# Decawave.net
KiCad netlist of a schematic drawn in Altium Designer
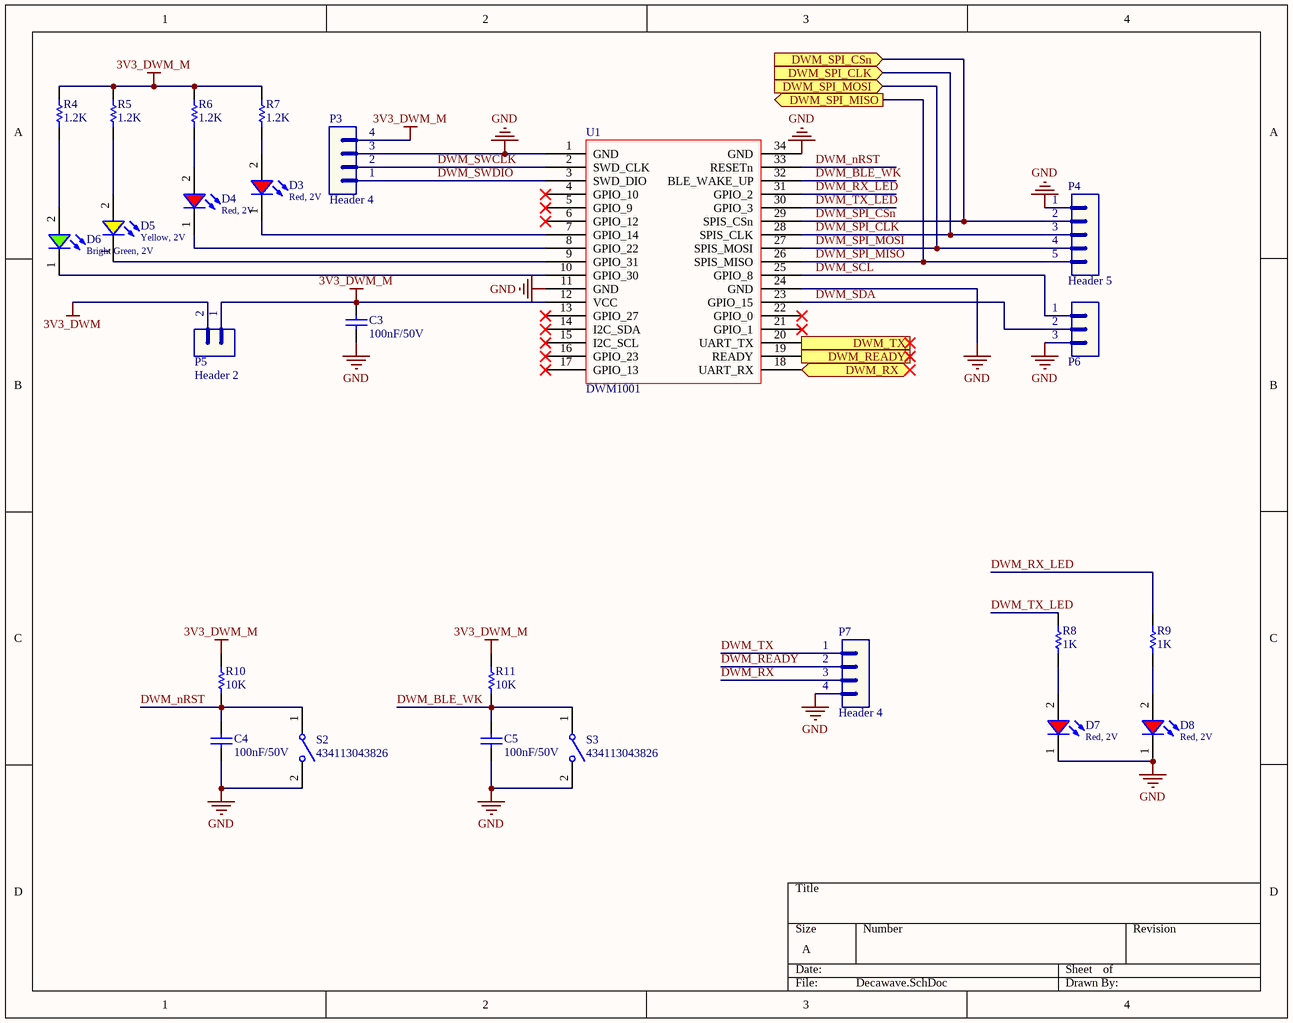
[diagram p0: Decawave.SchDoc]

(export (version "E")
  (design (tool "Eeschema 10.0.6"))
  (components
    (comp (ref "C3")
      (value "100nF/50V")
      (footprint "CAP-SM-0805")
      (description "CAP CER 0.1UF 50V Y5V 0805")
      (fields
        (field (name "MANUFACTURER") "Samsung Electro-Mechanics")
        (field (name "MANUFACTURER PART NUMBER") "CL21F104ZBCNNNC")
      )
      (libsource (lib "Capacitor") (part "Cap-100nF-50V-0805"))
    )
    (comp (ref "C4")
      (value "100nF/50V")
      (footprint "CAP-SM-0805")
      (description "CAP CER 0.1UF 50V Y5V 0805")
      (fields
        (field (name "MANUFACTURER") "Samsung Electro-Mechanics")
        (field (name "MANUFACTURER PART NUMBER") "CL21F104ZBCNNNC")
      )
      (libsource (lib "Capacitor") (part "Cap-100nF-50V-0805"))
    )
    (comp (ref "C5")
      (value "100nF/50V")
      (footprint "CAP-SM-0805")
      (description "CAP CER 0.1UF 50V Y5V 0805")
      (fields
        (field (name "MANUFACTURER") "Samsung Electro-Mechanics")
        (field (name "MANUFACTURER PART NUMBER") "CL21F104ZBCNNNC")
      )
      (libsource (lib "Capacitor") (part "Cap-100nF-50V-0805"))
    )
    (comp (ref "D3")
      (value "Red, 2V")
      (footprint "WL-SMCW_0805")
      (description "WL-SMCW SMT Mono-color Chip LED Waterclear, size 0805, Red, 2V, 140deg")
      (fields (field (name "PART NUMBER") "150080RS75000") (field (name "PUBLISHER") "Wurth Elektronik"))
      (libsource (lib "150080BS75000_Altium_WL-SMCW_rev20a") (part "150080RS75000"))
    )
    (comp (ref "D4")
      (value "Red, 2V")
      (footprint "WL-SMCW_0805")
      (description "WL-SMCW SMT Mono-color Chip LED Waterclear, size 0805, Red, 2V, 140deg")
      (fields (field (name "PART NUMBER") "150080RS75000") (field (name "PUBLISHER") "Wurth Elektronik"))
      (libsource (lib "150080BS75000_Altium_WL-SMCW_rev20a") (part "150080RS75000"))
    )
    (comp (ref "D5")
      (value "Yellow, 2V")
      (footprint "WL-SMCW_0805")
      (description "WL-SMCW SMT Mono-color Chip LED Waterclear, size 0805, Yellow, 2V, 140deg")
      (fields (field (name "PART NUMBER") "150080YS75000") (field (name "PUBLISHER") "Wurth Elektronik"))
      (libsource (lib "150080BS75000_Altium_WL-SMCW_rev20a") (part "150080YS75000"))
    )
    (comp (ref "D6")
      (value "Bright Green, 2V")
      (footprint "WL-SMCW_0805")
      (description "WL-SMCW SMT Mono-color Chip LED Waterclear, size 0805, Bright Green, 2V, 140deg")
      (fields (field (name "PART NUMBER") "150080VS75000") (field (name "PUBLISHER") "Wurth Elektronik"))
      (libsource (lib "150080BS75000_Altium_WL-SMCW_rev20a") (part "150080VS75000"))
    )
    (comp (ref "D7")
      (value "Red, 2V")
      (footprint "WL-SMCW_0805")
      (description "WL-SMCW SMT Mono-color Chip LED Waterclear, size 0805, Red, 2V, 140deg")
      (fields (field (name "PART NUMBER") "150080RS75000") (field (name "PUBLISHER") "Wurth Elektronik"))
      (libsource (lib "150080BS75000_Altium_WL-SMCW_rev20a") (part "150080RS75000"))
    )
    (comp (ref "D8")
      (value "Red, 2V")
      (footprint "WL-SMCW_0805")
      (description "WL-SMCW SMT Mono-color Chip LED Waterclear, size 0805, Red, 2V, 140deg")
      (fields (field (name "PART NUMBER") "150080RS75000") (field (name "PUBLISHER") "Wurth Elektronik"))
      (libsource (lib "150080BS75000_Altium_WL-SMCW_rev20a") (part "150080RS75000"))
    )
    (comp (ref "P3")
      (value "Header 4")
      (footprint "JP4")
      (description "Header, 4-Pin")
      (fields (field (name "PUBLISHER") "Altium Limited"))
      (libsource (lib "Header-connector") (part "Header 4"))
    )
    (comp (ref "P4")
      (value "Header 5")
      (footprint "JP5")
      (description "Header, 5-Pin")
      (fields (field (name "PUBLISHER") "Altium Limited"))
      (libsource (lib "Header-connector") (part "Header 5"))
    )
    (comp (ref "P5")
      (value "Header 2")
      (footprint "JP2")
      (description "Header, 2-Pin")
      (fields (field (name "PUBLISHER") "Altium Limited"))
      (libsource (lib "Header-connector") (part "Header 2"))
    )
    (comp (ref "P6")
      (value "Header 3")
      (footprint "JP3")
      (description "Header, 3-Pin")
      (fields (field (name "PUBLISHER") "Altium Limited"))
      (libsource (lib "Header-connector") (part "Header 3"))
    )
    (comp (ref "P7")
      (value "Header 4")
      (footprint "JP4")
      (description "Header, 4-Pin")
      (fields (field (name "PUBLISHER") "Altium Limited"))
      (libsource (lib "") (part "Header 4_1"))
    )
    (comp (ref "R4")
      (value "1.2K")
      (footprint "Resistor:RES-SM-0805")
      (description "RES SMD 1.2K OHM 1% 1/8W 0805")
      (fields
        (field (name "MANUFACTURER") "TE Connectivity Passive Product")
        (field (name "MANUFACTURER PART NUMBER") "CRG0805F1K2")
      )
      (libsource (lib "Resistor") (part "Res-1.2K-0805"))
    )
    (comp (ref "R5")
      (value "1.2K")
      (footprint "Resistor:RES-SM-0805")
      (description "RES SMD 1.2K OHM 1% 1/8W 0805")
      (fields
        (field (name "MANUFACTURER") "TE Connectivity Passive Product")
        (field (name "MANUFACTURER PART NUMBER") "CRG0805F1K2")
      )
      (libsource (lib "Resistor") (part "Res-1.2K-0805"))
    )
    (comp (ref "R6")
      (value "1.2K")
      (footprint "Resistor:RES-SM-0805")
      (description "RES SMD 1.2K OHM 1% 1/8W 0805")
      (fields
        (field (name "MANUFACTURER") "TE Connectivity Passive Product")
        (field (name "MANUFACTURER PART NUMBER") "CRG0805F1K2")
      )
      (libsource (lib "Resistor") (part "Res-1.2K-0805"))
    )
    (comp (ref "R7")
      (value "1.2K")
      (footprint "Resistor:RES-SM-0805")
      (description "RES SMD 1.2K OHM 1% 1/8W 0805")
      (fields
        (field (name "MANUFACTURER") "TE Connectivity Passive Product")
        (field (name "MANUFACTURER PART NUMBER") "CRG0805F1K2")
      )
      (libsource (lib "Resistor") (part "Res-1.2K-0805"))
    )
    (comp (ref "R8")
      (value "1K")
      (footprint "Resistor:RES-SM-0805")
      (description "RES 1K OHM 1% 1/4W 0805")
      (fields
        (field (name "MANUFACTURER") "Stackpole Electronics Inc")
        (field (name "MANUFACTURER PART NUMBER") "RNCP0805FTD1K00")
      )
      (libsource (lib "Resistor") (part "Res-1K-0805"))
    )
    (comp (ref "R9")
      (value "1K")
      (footprint "Resistor:RES-SM-0805")
      (description "RES 1K OHM 1% 1/4W 0805")
      (fields
        (field (name "MANUFACTURER") "Stackpole Electronics Inc")
        (field (name "MANUFACTURER PART NUMBER") "RNCP0805FTD1K00")
      )
      (libsource (lib "Resistor") (part "Res-1K-0805"))
    )
    (comp (ref "R10")
      (value "10K")
      (footprint "Resistor:RES-SM-0805")
      (description "RES 10K OHM 1% 1/4W 0805")
      (fields
        (field (name "MANUFACTURER") "Stackpole Electronics Inc")
        (field (name "MANUFACTURER PART NUMBER") "RNCP0805FTD10K0")
      )
      (libsource (lib "Resistor") (part "Res-10k-0805"))
    )
    (comp (ref "R11")
      (value "10K")
      (footprint "Resistor:RES-SM-0805")
      (description "RES 10K OHM 1% 1/4W 0805")
      (fields
        (field (name "MANUFACTURER") "Stackpole Electronics Inc")
        (field (name "MANUFACTURER PART NUMBER") "RNCP0805FTD10K0")
      )
      (libsource (lib "Resistor") (part "Res-10k-0805"))
    )
    (comp (ref "S2")
      (value "434113043826")
      (footprint "434113043826")
      (description "WS-TASV J-Bend SMT Tact Switch 6x3.5mm, height 4.3mm, 260gf")
      (fields (field (name "PUBLISHER") "Wurth Elektronik"))
      (libsource (lib "434113043826_Altium_WS-TASV_rev20a") (part "434113043826"))
    )
    (comp (ref "S3")
      (value "434113043826")
      (footprint "434113043826")
      (description "WS-TASV J-Bend SMT Tact Switch 6x3.5mm, height 4.3mm, 260gf")
      (fields (field (name "PUBLISHER") "Wurth Elektronik"))
      (libsource (lib "434113043826_Altium_WS-TASV_rev20a") (part "434113043826"))
    )
    (comp (ref "U1") (value "DWM1001") (footprint "DWM1001") (libsource (lib "chicken") (part "DWM1001")))
  )
  (nets
    (net (code "1") (name "/DWM_BLE_WK") (class "Default")
      (node (ref "C5") (pin "2") (pinfunction "2_2") (pintype "passive"))
      (node (ref "R11") (pin "2") (pinfunction "2_2") (pintype "passive"))
      (node (ref "S3") (pin "1") (pinfunction "1_1") (pintype "passive"))
      (node (ref "U1") (pin "32") (pinfunction "BLE_WAKE_UP_32") (pintype "passive"))
    )
    (net (code "2") (name "/DWM_READY") (class "Default")
      (node (ref "P7") (pin "2") (pinfunction "2_2") (pintype "passive"))
    )
    (net (code "3") (name "/DWM_RX") (class "Default")
      (node (ref "P7") (pin "3") (pinfunction "3_3") (pintype "passive"))
    )
    (net (code "4") (name "/DWM_RX_LED") (class "Default")
      (node (ref "R9") (pin "2") (pinfunction "2_2") (pintype "passive"))
      (node (ref "U1") (pin "31") (pinfunction "GPIO_2_31") (pintype "passive"))
    )
    (net (code "5") (name "/DWM_SCL") (class "Default")
      (node (ref "P6") (pin "1") (pinfunction "1_1") (pintype "passive"))
      (node (ref "U1") (pin "25") (pinfunction "GPIO_8_25") (pintype "passive"))
    )
    (net (code "6") (name "/DWM_SDA") (class "Default")
      (node (ref "P6") (pin "2") (pinfunction "2_2") (pintype "passive"))
      (node (ref "U1") (pin "23") (pinfunction "GPIO_15_23") (pintype "passive"))
    )
    (net (code "7") (name "/DWM_SPI_CLK") (class "Default")
      (node (ref "P4") (pin "3") (pinfunction "3_3") (pintype "passive"))
      (node (ref "U1") (pin "28") (pinfunction "SPIS_CLK_28") (pintype "passive"))
    )
    (net (code "8") (name "/DWM_SPI_CSn") (class "Default")
      (node (ref "P4") (pin "2") (pinfunction "2_2") (pintype "passive"))
      (node (ref "U1") (pin "29") (pinfunction "SPIS_CSn_29") (pintype "passive"))
    )
    (net (code "9") (name "/DWM_SPI_MISO") (class "Default")
      (node (ref "P4") (pin "5") (pinfunction "5_5") (pintype "passive"))
      (node (ref "U1") (pin "26") (pinfunction "SPIS_MISO_26") (pintype "passive"))
    )
    (net (code "10") (name "/DWM_SPI_MOSI") (class "Default")
      (node (ref "P4") (pin "4") (pinfunction "4_4") (pintype "passive"))
      (node (ref "U1") (pin "27") (pinfunction "SPIS_MOSI_27") (pintype "passive"))
    )
    (net (code "11") (name "/DWM_SWCLK") (class "Default")
      (node (ref "P3") (pin "2") (pinfunction "2_2") (pintype "passive"))
      (node (ref "U1") (pin "2") (pinfunction "SWD_CLK_2") (pintype "passive"))
    )
    (net (code "12") (name "/DWM_SWDIO") (class "Default")
      (node (ref "P3") (pin "1") (pinfunction "1_1") (pintype "passive"))
      (node (ref "U1") (pin "3") (pinfunction "SWD_DIO_3") (pintype "passive"))
    )
    (net (code "13") (name "/DWM_TX") (class "Default")
      (node (ref "P7") (pin "1") (pinfunction "1_1") (pintype "passive"))
    )
    (net (code "14") (name "/DWM_TX_LED") (class "Default")
      (node (ref "R8") (pin "2") (pinfunction "2_2") (pintype "passive"))
      (node (ref "U1") (pin "30") (pinfunction "GPIO_3_30") (pintype "passive"))
    )
    (net (code "15") (name "/DWM_nRST") (class "Default")
      (node (ref "C4") (pin "2") (pinfunction "2_2") (pintype "passive"))
      (node (ref "R10") (pin "2") (pinfunction "2_2") (pintype "passive"))
      (node (ref "S2") (pin "1") (pinfunction "1_1") (pintype "passive"))
      (node (ref "U1") (pin "33") (pinfunction "RESETn_33") (pintype "passive"))
    )
    (net (code "16") (name "3V3_DWM") (class "Default")
      (node (ref "P5") (pin "2") (pinfunction "2_2") (pintype "passive"))
    )
    (net (code "17") (name "3V3_DWM_M") (class "Default")
      (node (ref "C3") (pin "2") (pinfunction "2_2") (pintype "passive"))
      (node (ref "P3") (pin "4") (pinfunction "4_4") (pintype "passive"))
      (node (ref "P5") (pin "1") (pinfunction "1_1") (pintype "passive"))
      (node (ref "R10") (pin "1") (pinfunction "1_1") (pintype "passive"))
      (node (ref "R11") (pin "1") (pinfunction "1_1") (pintype "passive"))
      (node (ref "R4") (pin "2") (pinfunction "2_2") (pintype "passive"))
      (node (ref "R5") (pin "2") (pinfunction "2_2") (pintype "passive"))
      (node (ref "R6") (pin "2") (pinfunction "2_2") (pintype "passive"))
      (node (ref "R7") (pin "2") (pinfunction "2_2") (pintype "passive"))
      (node (ref "U1") (pin "12") (pinfunction "VCC_12") (pintype "passive"))
    )
    (net (code "18") (name "GND") (class "Default")
      (node (ref "C3") (pin "1") (pinfunction "1_1") (pintype "passive"))
      (node (ref "C4") (pin "1") (pinfunction "1_1") (pintype "passive"))
      (node (ref "C5") (pin "1") (pinfunction "1_1") (pintype "passive"))
      (node (ref "D7") (pin "1") (pinfunction "K_1") (pintype "passive"))
      (node (ref "D8") (pin "1") (pinfunction "K_1") (pintype "passive"))
      (node (ref "P3") (pin "3") (pinfunction "3_3") (pintype "passive"))
      (node (ref "P4") (pin "1") (pinfunction "1_1") (pintype "passive"))
      (node (ref "P6") (pin "3") (pinfunction "3_3") (pintype "passive"))
      (node (ref "P7") (pin "4") (pinfunction "4_4") (pintype "passive"))
      (node (ref "S2") (pin "2") (pinfunction "2_2") (pintype "passive"))
      (node (ref "S3") (pin "2") (pinfunction "2_2") (pintype "passive"))
      (node (ref "U1") (pin "1") (pinfunction "GND_1") (pintype "passive"))
      (node (ref "U1") (pin "11") (pinfunction "GND_11") (pintype "passive"))
      (node (ref "U1") (pin "24") (pinfunction "GND_24") (pintype "passive"))
      (node (ref "U1") (pin "34") (pinfunction "GND_34") (pintype "passive"))
    )
    (net (code "19") (name "Net-(D3-A)") (class "Default")
      (node (ref "D3") (pin "2") (pinfunction "A_2") (pintype "passive"))
      (node (ref "R7") (pin "1") (pinfunction "1_1") (pintype "passive"))
    )
    (net (code "20") (name "Net-(D3-K)") (class "Default")
      (node (ref "D3") (pin "1") (pinfunction "K_1") (pintype "passive"))
      (node (ref "U1") (pin "7") (pinfunction "GPIO_14_7") (pintype "passive"))
    )
    (net (code "21") (name "Net-(D4-A)") (class "Default")
      (node (ref "D4") (pin "2") (pinfunction "A_2") (pintype "passive"))
      (node (ref "R6") (pin "1") (pinfunction "1_1") (pintype "passive"))
    )
    (net (code "22") (name "Net-(D4-K)") (class "Default")
      (node (ref "D4") (pin "1") (pinfunction "K_1") (pintype "passive"))
      (node (ref "U1") (pin "8") (pinfunction "GPIO_22_8") (pintype "passive"))
    )
    (net (code "23") (name "Net-(D5-A)") (class "Default")
      (node (ref "D5") (pin "2") (pinfunction "A_2") (pintype "passive"))
      (node (ref "R5") (pin "1") (pinfunction "1_1") (pintype "passive"))
    )
    (net (code "24") (name "Net-(D5-K)") (class "Default")
      (node (ref "D5") (pin "1") (pinfunction "K_1") (pintype "passive"))
      (node (ref "U1") (pin "9") (pinfunction "GPIO_31_9") (pintype "passive"))
    )
    (net (code "25") (name "Net-(D6-A)") (class "Default")
      (node (ref "D6") (pin "2") (pinfunction "A_2") (pintype "passive"))
      (node (ref "R4") (pin "1") (pinfunction "1_1") (pintype "passive"))
    )
    (net (code "26") (name "Net-(D6-K)") (class "Default")
      (node (ref "D6") (pin "1") (pinfunction "K_1") (pintype "passive"))
      (node (ref "U1") (pin "10") (pinfunction "GPIO_30_10") (pintype "passive"))
    )
    (net (code "27") (name "Net-(D7-A)") (class "Default")
      (node (ref "D7") (pin "2") (pinfunction "A_2") (pintype "passive"))
      (node (ref "R8") (pin "1") (pinfunction "1_1") (pintype "passive"))
    )
    (net (code "28") (name "Net-(D8-A)") (class "Default")
      (node (ref "D8") (pin "2") (pinfunction "A_2") (pintype "passive"))
      (node (ref "R9") (pin "1") (pinfunction "1_1") (pintype "passive"))
    )
    (net (code "29") (name "unconnected-(U1-GPIO_0-Pad22)") (class "Default")
      (node (ref "U1") (pin "22") (pinfunction "GPIO_0_22") (pintype "passive+no_connect"))
    )
    (net (code "30") (name "unconnected-(U1-GPIO_1-Pad21)") (class "Default")
      (node (ref "U1") (pin "21") (pinfunction "GPIO_1_21") (pintype "passive+no_connect"))
    )
    (net (code "31") (name "unconnected-(U1-GPIO_9-Pad5)") (class "Default")
      (node (ref "U1") (pin "5") (pinfunction "GPIO_9_5") (pintype "passive+no_connect"))
    )
    (net (code "32") (name "unconnected-(U1-GPIO_10-Pad4)") (class "Default")
      (node (ref "U1") (pin "4") (pinfunction "GPIO_10_4") (pintype "passive+no_connect"))
    )
    (net (code "33") (name "unconnected-(U1-GPIO_12-Pad6)") (class "Default")
      (node (ref "U1") (pin "6") (pinfunction "GPIO_12_6") (pintype "passive+no_connect"))
    )
    (net (code "34") (name "unconnected-(U1-GPIO_13-Pad17)") (class "Default")
      (node (ref "U1") (pin "17") (pinfunction "GPIO_13_17") (pintype "passive+no_connect"))
    )
    (net (code "35") (name "unconnected-(U1-GPIO_23-Pad16)") (class "Default")
      (node (ref "U1") (pin "16") (pinfunction "GPIO_23_16") (pintype "passive+no_connect"))
    )
    (net (code "36") (name "unconnected-(U1-GPIO_27-Pad13)") (class "Default")
      (node (ref "U1") (pin "13") (pinfunction "GPIO_27_13") (pintype "passive+no_connect"))
    )
    (net (code "37") (name "unconnected-(U1-I2C_SCL-Pad15)") (class "Default")
      (node (ref "U1") (pin "15") (pinfunction "I2C_SCL_15") (pintype "passive+no_connect"))
    )
    (net (code "38") (name "unconnected-(U1-I2C_SDA-Pad14)") (class "Default")
      (node (ref "U1") (pin "14") (pinfunction "I2C_SDA_14") (pintype "passive+no_connect"))
    )
    (net (code "39") (name "unconnected-(U1-READY-Pad19)") (class "Default")
      (node (ref "U1") (pin "19") (pinfunction "READY_19") (pintype "passive"))
    )
    (net (code "40") (name "unconnected-(U1-UART_RX-Pad18)") (class "Default")
      (node (ref "U1") (pin "18") (pinfunction "UART_RX_18") (pintype "passive"))
    )
    (net (code "41") (name "unconnected-(U1-UART_TX-Pad20)") (class "Default")
      (node (ref "U1") (pin "20") (pinfunction "UART_TX_20") (pintype "passive"))
    )
  )
)
